# STM32_BOARD_v1a_powerSupply.net
KiCad netlist of a schematic drawn in Altium Designer
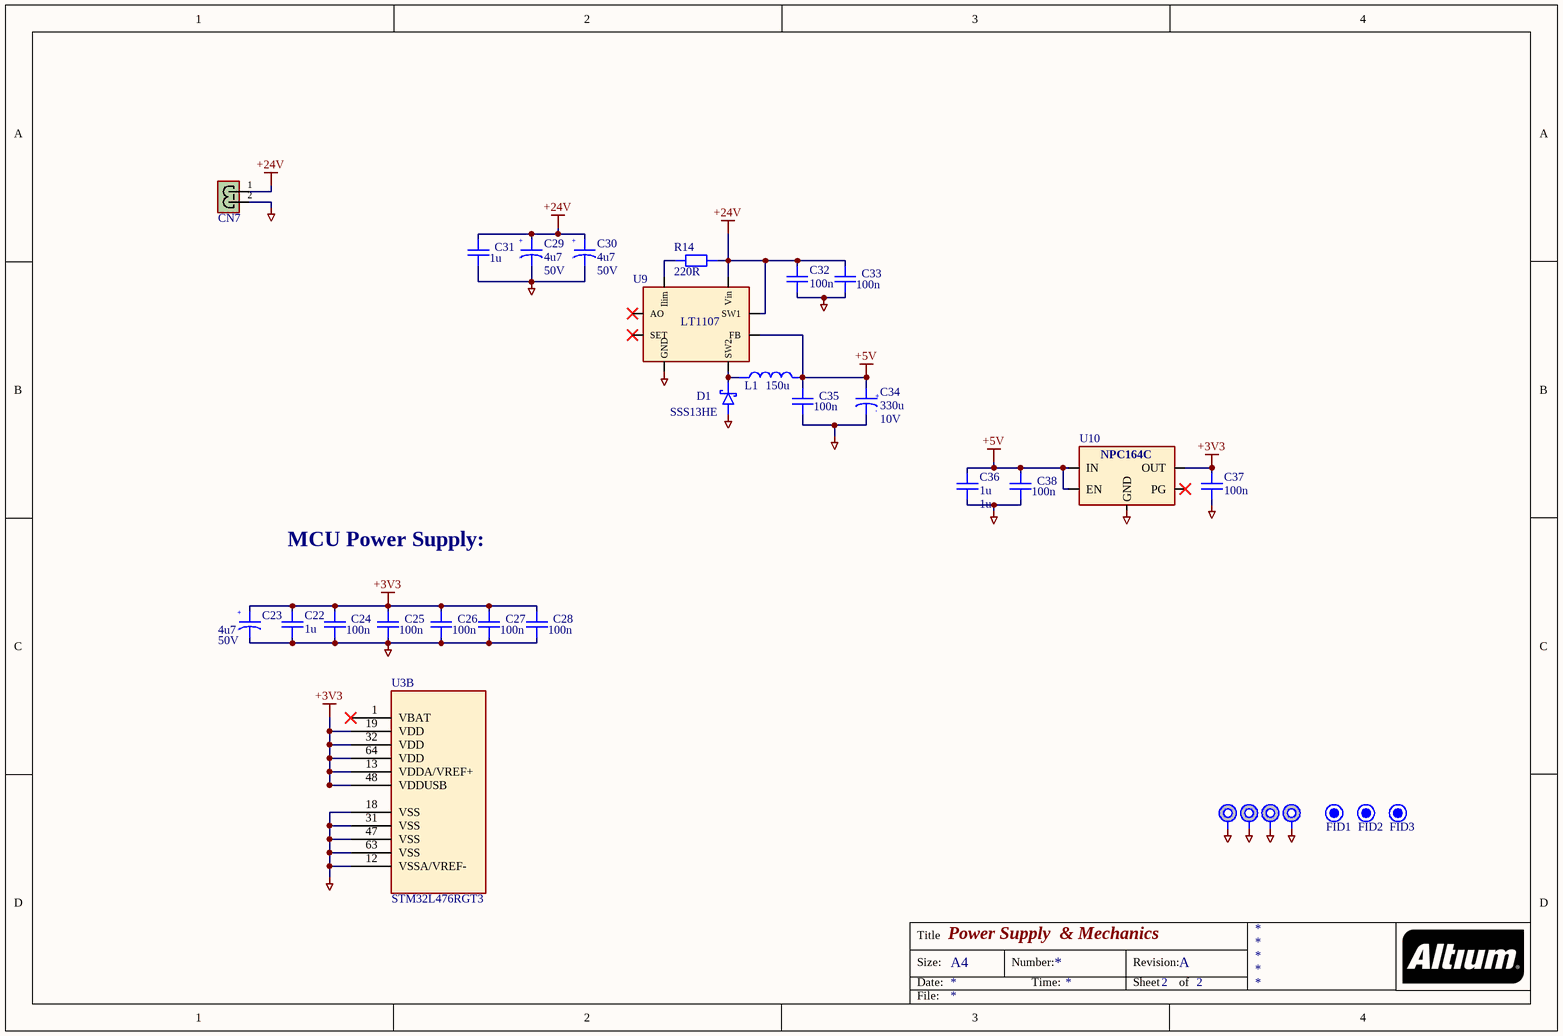
[diagram p0: STM32_BOARD_v1a_powerSupply.SchDoc]

(export (version "E")
  (design (tool "Eeschema 10.0.6"))
  (components
    (comp (ref "C22") (value "1u") (footprint "CAP_SMD") (libsource (lib "Miscellanous") (part "C")))
    (comp (ref "C23")
      (value "4u7")
      (footprint "865230642008")
      (description "SMD Aluminium Electrolytic Capacitor, Radial Can - SMD, 4.7 µF, 50 V, 5000 hours @ 105°C, Polar")
      (fields
        (field (name "MANUFACTURER") "Wurth Elektrinik")
        (field (name "MFR PART NUM") "865230642008")
        (field (name "VOLTAGE") "50V")
      )
      (libsource (lib "electrolyticCapacitors") (part "CAP_POLAR_4u7_50V"))
    )
    (comp (ref "C24") (value "100n") (footprint "CAP_SMD") (libsource (lib "Miscellanous") (part "C")))
    (comp (ref "C25") (value "100n") (footprint "CAP_SMD") (libsource (lib "Miscellanous") (part "C")))
    (comp (ref "C26") (value "100n") (footprint "CAP_SMD") (libsource (lib "Miscellanous") (part "C")))
    (comp (ref "C27") (value "100n") (footprint "CAP_SMD") (libsource (lib "Miscellanous") (part "C")))
    (comp (ref "C28") (value "100n") (footprint "CAP_SMD") (libsource (lib "Miscellanous") (part "C")))
    (comp (ref "C29")
      (value "4u7")
      (footprint "865230642008")
      (description "SMD Aluminium Electrolytic Capacitor, Radial Can - SMD, 4.7 µF, 50 V, 5000 hours @ 105°C, Polar")
      (fields
        (field (name "MANUFACTURER") "Wurth Elektrinik")
        (field (name "MFR PART NUM") "865230642008")
        (field (name "VOLTAGE") "50V")
      )
      (libsource (lib "electrolyticCapacitors") (part "CAP_POLAR_4u7_50V"))
    )
    (comp (ref "C30")
      (value "4u7")
      (footprint "865230642008")
      (description "SMD Aluminium Electrolytic Capacitor, Radial Can - SMD, 4.7 µF, 50 V, 5000 hours @ 105°C, Polar")
      (fields
        (field (name "MANUFACTURER") "Wurth Elektrinik")
        (field (name "MFR PART NUM") "865230642008")
        (field (name "VOLTAGE") "50V")
      )
      (libsource (lib "electrolyticCapacitors") (part "CAP_POLAR_4u7_50V"))
    )
    (comp (ref "C31") (value "1u") (footprint "CAP_SMD") (libsource (lib "Miscellanous") (part "C")))
    (comp (ref "C32") (value "100n") (footprint "CAP_SMD") (libsource (lib "Miscellanous") (part "C")))
    (comp (ref "C33") (value "100n") (footprint "CAP_SMD") (libsource (lib "Miscellanous") (part "C")))
    (comp (ref "C34")
      (value "330u")
      (footprint "CAPAE10083X105M")
      (description "SMD Aluminium Electrolytic Capacitor, Radial Can - SMD, 4.7 µF, 50 V, 5000 hours @ 105°C, Polar")
      (fields
        (field (name "MANUFACTURER") "Kemet")
        (field (name "MFR PART NUM") "EDK337M010A9MAA")
        (field (name "VOLTAGE") "10V")
      )
      (libsource (lib "electrolyticCapacitors") (part "CAP_POLAR_330u_50V"))
    )
    (comp (ref "C35") (value "100n") (footprint "CAP_SMD") (libsource (lib "Miscellanous") (part "C")))
    (comp (ref "C36")
      (value "1u")
      (footprint "CAP_SMD")
      (fields (field (name "CAPACITANCE") "1u"))
      (libsource (lib "Miscellanous") (part "C"))
    )
    (comp (ref "C37") (value "100n") (footprint "CAP_SMD") (libsource (lib "Miscellanous") (part "C")))
    (comp (ref "C38") (value "100n") (footprint "CAP_SMD") (libsource (lib "Miscellanous") (part "C")))
    (comp (ref "CN7")
      (value "PHOENIX_CONTACT_2x1_")
      (footprint "1755516")
      (description "Pin header, straight, Straight, 5mm Pitch, 2 Poles, Phoenix Contact")
      (fields (field (name "MANUFACTURER") "Phoenix Contact"))
      (libsource (lib "Connectors") (part "PHOENIX_CONTACT_2x1_"))
    )
    (comp (ref "D1")
      (value "SSS13HE")
      (footprint "SOD-323HE")
      (description "Surface Mount Schottky Barrier Rectifier.")
      (fields (field (name "MANUFACTURER") "ON Semiconductor"))
      (libsource (lib "Diodes") (part "SS13HE"))
    )
    (comp (ref "FID1")
      (value "FID-2mm")
      (footprint "fid-2mm")
      (libsource (lib "Miscellanous") (part "FID-2mm"))
    )
    (comp (ref "FID2")
      (value "FID-2mm")
      (footprint "fid-2mm")
      (libsource (lib "Miscellanous") (part "FID-2mm"))
    )
    (comp (ref "FID3")
      (value "FID-2mm")
      (footprint "fid-2mm")
      (libsource (lib "Miscellanous") (part "FID-2mm"))
    )
    (comp (ref "L1")
      (value "150u")
      (footprint "744770215")
      (description "Power Inductor (SMD), 150 µH, 1.8 A, Shielded, 1.8 A, WE-PD, 12mm x 12mm x 8mm")
      (fields (field (name "MANUFACTURER") "Wurth Elektronik"))
      (libsource (lib "Inductors") (part "L_105uH_744770215"))
    )
    (comp (ref "MH1")
      (value "Mounting hole, non-plated, 2.2mm")
      (footprint "MH-2mm2")
      (libsource (lib "Miscellanous") (part "MH-2mm2"))
    )
    (comp (ref "MH2")
      (value "Mounting hole, non-plated, 2.2mm")
      (footprint "MH-2mm2")
      (libsource (lib "Miscellanous") (part "MH-2mm2"))
    )
    (comp (ref "MH3")
      (value "Mounting hole, non-plated, 2.2mm")
      (footprint "MH-2mm2")
      (libsource (lib "Miscellanous") (part "MH-2mm2"))
    )
    (comp (ref "MH4")
      (value "Mounting hole, non-plated, 2.2mm")
      (footprint "MH-2mm2")
      (libsource (lib "Miscellanous") (part "MH-2mm2"))
    )
    (comp (ref "R14") (value "220R") (footprint "RES_0805") (libsource (lib "Miscellanous") (part "R")))
    (comp (ref "U3")
      (value "32-bit Microcontroller")
      (footprint "LQFP64_10x10mm")
      (description "STM32 Arm-based 32-bit Microcontroller")
      (fields
        (field (name "MFR PART NUM") "STM32L476RGT3")
        (field (name "MANUFACTURER") "STMicroelectronics")
      )
      (libsource (lib "IC_Digital") (part "STM32L476RGT3"))
    )
    (comp (ref "U9")
      (value "LT1107")
      (footprint "SOIC127P600X175-8N")
      (description "Micropower\r\nDC/DC Converter\r\nAdjustable and Fixed 5V, 12V")
      (fields (field (name "MANUFACTURER") "Linear technology"))
      (libsource (lib "IC_PowerSupply") (part "LT1107"))
    )
    (comp (ref "U10")
      (value "NCP164C")
      (footprint "NCP164C_TSOP-5")
      (description "LDO Regulator, 300mA,\r\nLow Dropout Voltage, Ultra Low Noise, High PSRR with Power Good")
      (fields (field (name "MANUFACTURER") "On Semiconductor"))
      (libsource (lib "IC_PowerSupply") (part "NCP164C"))
    )
  )
  (nets
    (net (code "1") (name "+3V3") (class "Default")
      (node (ref "C22") (pin "2") (pinfunction "Pin_2_2") (pintype "passive"))
      (node (ref "C23") (pin "1") (pinfunction "Pin_1_1") (pintype "passive"))
      (node (ref "C24") (pin "2") (pinfunction "Pin_2_2") (pintype "passive"))
      (node (ref "C25") (pin "2") (pinfunction "Pin_2_2") (pintype "passive"))
      (node (ref "C26") (pin "2") (pinfunction "Pin_2_2") (pintype "passive"))
      (node (ref "C27") (pin "2") (pinfunction "Pin_2_2") (pintype "passive"))
      (node (ref "C28") (pin "2") (pinfunction "Pin_2_2") (pintype "passive"))
      (node (ref "C37") (pin "2") (pinfunction "Pin_2_2") (pintype "passive"))
      (node (ref "U10") (pin "5") (pinfunction "OUT_5") (pintype "power_in"))
      (node (ref "U3") (pin "13") (pinfunction "VDDA/VREF+_13") (pintype "power_in"))
      (node (ref "U3") (pin "19") (pinfunction "VDD_19") (pintype "power_in"))
      (node (ref "U3") (pin "32") (pinfunction "VDD_32") (pintype "power_in"))
      (node (ref "U3") (pin "48") (pinfunction "VDDUSB_48") (pintype "power_in"))
      (node (ref "U3") (pin "64") (pinfunction "VDD_64") (pintype "power_in"))
    )
    (net (code "2") (name "+5V") (class "Default")
      (node (ref "C34") (pin "1") (pinfunction "Pin_1_1") (pintype "passive"))
      (node (ref "C35") (pin "2") (pinfunction "Pin_2_2") (pintype "passive"))
      (node (ref "C36") (pin "2") (pinfunction "Pin_2_2") (pintype "passive"))
      (node (ref "C38") (pin "2") (pinfunction "Pin_2_2") (pintype "passive"))
      (node (ref "L1") (pin "2") (pinfunction "Pin_2_2") (pintype "passive"))
      (node (ref "U10") (pin "1") (pinfunction "IN_1") (pintype "power_in"))
      (node (ref "U10") (pin "3") (pinfunction "EN_3") (pintype "power_in"))
      (node (ref "U9") (pin "8") (pinfunction "FB_8") (pintype "passive"))
    )
    (net (code "3") (name "+24V") (class "Default")
      (node (ref "C29") (pin "1") (pinfunction "Pin_1_1") (pintype "passive"))
      (node (ref "C30") (pin "1") (pinfunction "Pin_1_1") (pintype "passive"))
      (node (ref "C31") (pin "2") (pinfunction "Pin_2_2") (pintype "passive"))
      (node (ref "C32") (pin "2") (pinfunction "Pin_2_2") (pintype "passive"))
      (node (ref "C33") (pin "2") (pinfunction "Pin_2_2") (pintype "passive"))
      (node (ref "CN7") (pin "1") (pinfunction "Pin_1_1") (pintype "passive"))
      (node (ref "R14") (pin "1") (pinfunction "Pin_1_1") (pintype "passive"))
      (node (ref "U9") (pin "2") (pinfunction "Vin_2") (pintype "power_in"))
      (node (ref "U9") (pin "3") (pinfunction "SW1_3") (pintype "power_in"))
    )
    (net (code "4") (name "GND") (class "Default")
      (node (ref "C22") (pin "1") (pinfunction "Pin_1_1") (pintype "passive"))
      (node (ref "C23") (pin "2") (pinfunction "Pin_2_2") (pintype "passive"))
      (node (ref "C24") (pin "1") (pinfunction "Pin_1_1") (pintype "passive"))
      (node (ref "C25") (pin "1") (pinfunction "Pin_1_1") (pintype "passive"))
      (node (ref "C26") (pin "1") (pinfunction "Pin_1_1") (pintype "passive"))
      (node (ref "C27") (pin "1") (pinfunction "Pin_1_1") (pintype "passive"))
      (node (ref "C28") (pin "1") (pinfunction "Pin_1_1") (pintype "passive"))
      (node (ref "C29") (pin "2") (pinfunction "Pin_2_2") (pintype "passive"))
      (node (ref "C30") (pin "2") (pinfunction "Pin_2_2") (pintype "passive"))
      (node (ref "C31") (pin "1") (pinfunction "Pin_1_1") (pintype "passive"))
      (node (ref "C32") (pin "1") (pinfunction "Pin_1_1") (pintype "passive"))
      (node (ref "C33") (pin "1") (pinfunction "Pin_1_1") (pintype "passive"))
      (node (ref "C34") (pin "2") (pinfunction "Pin_2_2") (pintype "passive"))
      (node (ref "C35") (pin "1") (pinfunction "Pin_1_1") (pintype "passive"))
      (node (ref "C36") (pin "1") (pinfunction "Pin_1_1") (pintype "passive"))
      (node (ref "C37") (pin "1") (pinfunction "Pin_1_1") (pintype "passive"))
      (node (ref "C38") (pin "1") (pinfunction "Pin_1_1") (pintype "passive"))
      (node (ref "CN7") (pin "2") (pinfunction "Pin_2_2") (pintype "passive"))
      (node (ref "D1") (pin "2") (pinfunction "A_2") (pintype "passive"))
      (node (ref "MH1") (pin "1") (pinfunction "Pin1_1") (pintype "power_in"))
      (node (ref "MH2") (pin "1") (pinfunction "Pin1_1") (pintype "power_in"))
      (node (ref "MH3") (pin "1") (pinfunction "Pin1_1") (pintype "power_in"))
      (node (ref "MH4") (pin "1") (pinfunction "Pin1_1") (pintype "power_in"))
      (node (ref "U10") (pin "2") (pinfunction "GND_2") (pintype "power_in"))
      (node (ref "U3") (pin "12") (pinfunction "VSSA/VREF-_12") (pintype "power_in"))
      (node (ref "U3") (pin "18") (pinfunction "VSS_18") (pintype "power_in"))
      (node (ref "U3") (pin "31") (pinfunction "VSS_31") (pintype "power_in"))
      (node (ref "U3") (pin "47") (pinfunction "VSS_47") (pintype "power_in"))
      (node (ref "U3") (pin "63") (pinfunction "VSS_63") (pintype "power_in"))
      (node (ref "U9") (pin "5") (pinfunction "GND_5") (pintype "passive"))
    )
    (net (code "5") (name "Net-(D1-C)") (class "Default")
      (node (ref "D1") (pin "1") (pinfunction "C_1") (pintype "passive"))
      (node (ref "L1") (pin "1") (pinfunction "Pin_1_1") (pintype "passive"))
      (node (ref "U9") (pin "4") (pinfunction "SW2_4") (pintype "power_in"))
    )
    (net (code "6") (name "Net-(R14-Pin_2)") (class "Default")
      (node (ref "R14") (pin "2") (pinfunction "Pin_2_2") (pintype "passive"))
      (node (ref "U9") (pin "1") (pinfunction "Ilim_1") (pintype "passive"))
    )
    (net (code "7") (name "unconnected-(U3B-VBAT-Pad1)") (class "Default")
      (node (ref "U3") (pin "1") (pinfunction "VBAT_1") (pintype "power_in+no_connect"))
    )
    (net (code "8") (name "unconnected-(U9-AO-Pad6)") (class "Default")
      (node (ref "U9") (pin "6") (pinfunction "AO_6") (pintype "passive+no_connect"))
    )
    (net (code "9") (name "unconnected-(U9-SET-Pad7)") (class "Default")
      (node (ref "U9") (pin "7") (pinfunction "SET_7") (pintype "passive+no_connect"))
    )
    (net (code "10") (name "unconnected-(U10-PG-Pad4)") (class "Default")
      (node (ref "U10") (pin "4") (pinfunction "PG_4") (pintype "power_in+no_connect"))
    )
  )
)
